# Integrated_Platform_Controller.net
KiCad netlist of a schematic drawn in Altium Designer
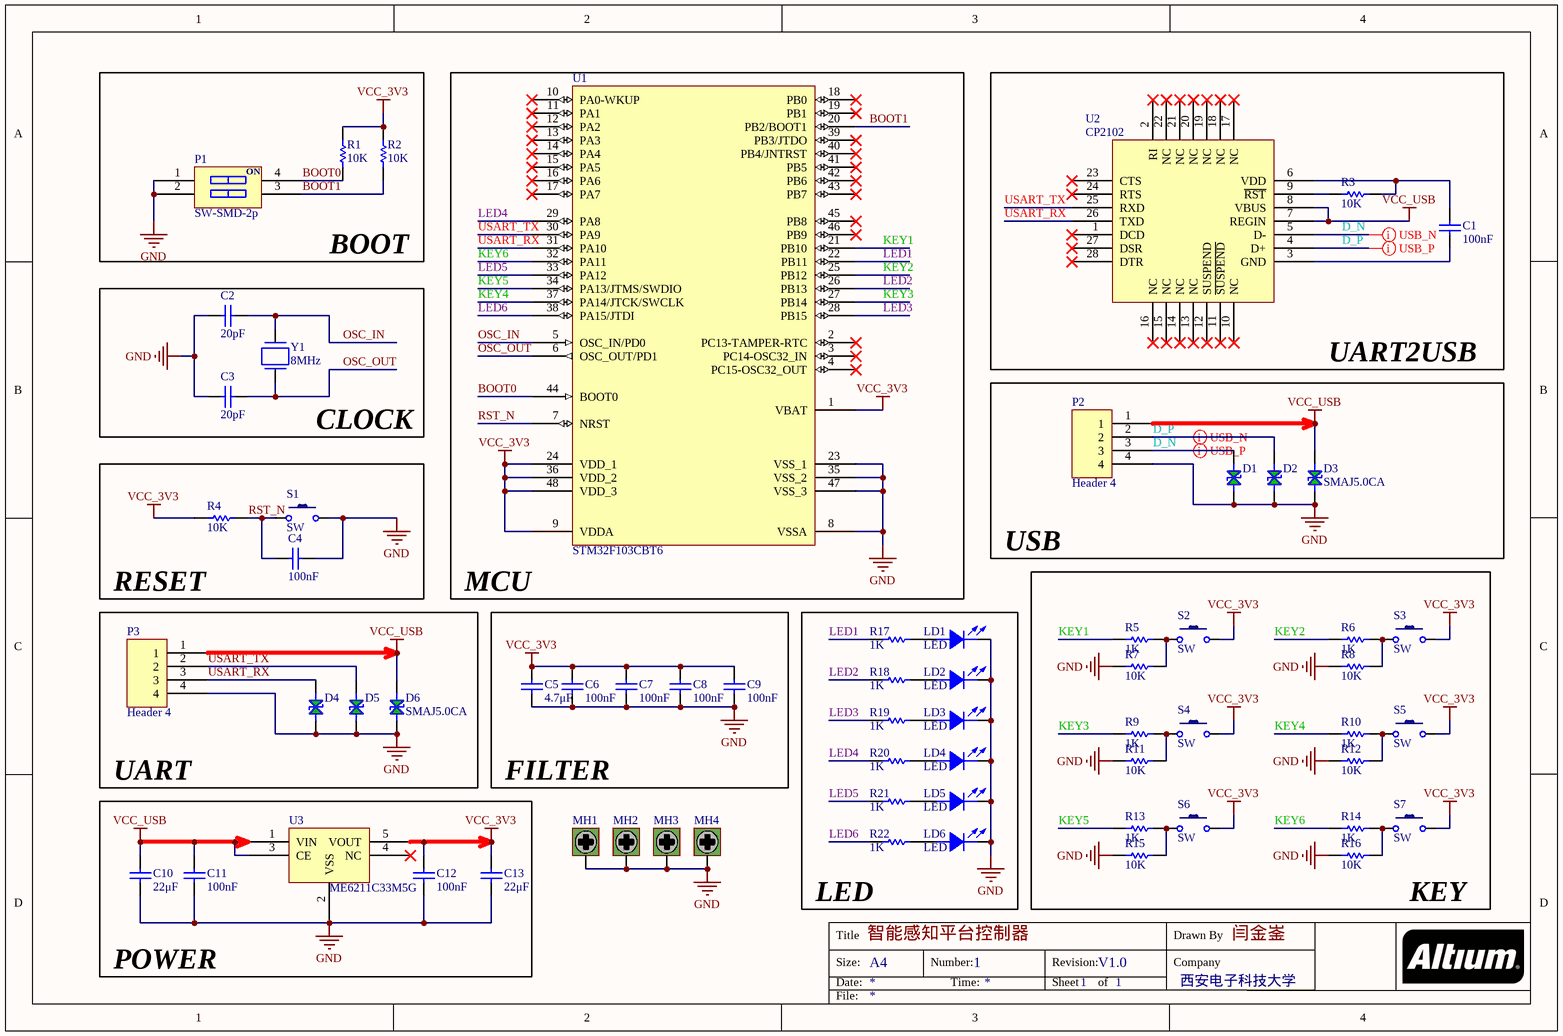
[diagram p0: Integrated_Platform_Controller.SchDoc]

(export (version "E")
  (design (tool "Eeschema 10.0.6"))
  (components
    (comp (ref "C1")
      (value "100nF")
      (footprint "C-0603")
      (description "Capacitor")
      (fields (field (name "PUBLISHER") "Altium Limited"))
      (libsource (lib "Verdvana_Library") (part "CAP"))
    )
    (comp (ref "C2")
      (value "20pF")
      (footprint "C-0603")
      (description "Capacitor")
      (fields (field (name "PUBLISHER") "Altium Limited"))
      (libsource (lib "Verdvana_Library") (part "CAP"))
    )
    (comp (ref "C3")
      (value "20pF")
      (footprint "C-0603")
      (description "Capacitor")
      (fields (field (name "PUBLISHER") "Altium Limited"))
      (libsource (lib "Verdvana_Library") (part "CAP"))
    )
    (comp (ref "C4")
      (value "100nF")
      (footprint "C-0603")
      (description "Capacitor")
      (fields (field (name "PUBLISHER") "Altium Limited"))
      (libsource (lib "Verdvana_Library") (part "CAP"))
    )
    (comp (ref "C5")
      (value "4.7μF")
      (footprint "C-0805")
      (description "Capacitor")
      (fields (field (name "PUBLISHER") "Altium Limited"))
      (libsource (lib "Verdvana_Library") (part "CAP"))
    )
    (comp (ref "C6")
      (value "100nF")
      (footprint "C-0603")
      (description "Capacitor")
      (fields (field (name "PUBLISHER") "Altium Limited"))
      (libsource (lib "Verdvana_Library") (part "CAP"))
    )
    (comp (ref "C7")
      (value "100nF")
      (footprint "C-0603")
      (description "Capacitor")
      (fields (field (name "PUBLISHER") "Altium Limited"))
      (libsource (lib "Verdvana_Library") (part "CAP"))
    )
    (comp (ref "C8")
      (value "100nF")
      (footprint "C-0603")
      (description "Capacitor")
      (fields (field (name "PUBLISHER") "Altium Limited"))
      (libsource (lib "Verdvana_Library") (part "CAP"))
    )
    (comp (ref "C9")
      (value "100nF")
      (footprint "C-0603")
      (description "Capacitor")
      (fields (field (name "PUBLISHER") "Altium Limited"))
      (libsource (lib "Verdvana_Library") (part "CAP"))
    )
    (comp (ref "C10")
      (value "22μF")
      (footprint "C-0805")
      (description "Capacitor")
      (fields (field (name "PUBLISHER") "Altium Limited"))
      (libsource (lib "Verdvana_Library") (part "CAP"))
    )
    (comp (ref "C11")
      (value "100nF")
      (footprint "C-0603")
      (description "Capacitor")
      (fields (field (name "PUBLISHER") "Altium Limited"))
      (libsource (lib "Verdvana_Library") (part "CAP"))
    )
    (comp (ref "C12")
      (value "100nF")
      (footprint "C-0603")
      (description "Capacitor")
      (fields (field (name "PUBLISHER") "Altium Limited"))
      (libsource (lib "Verdvana_Library") (part "CAP"))
    )
    (comp (ref "C13")
      (value "22μF")
      (footprint "C-0805")
      (description "Capacitor")
      (fields (field (name "PUBLISHER") "Altium Limited"))
      (libsource (lib "Verdvana_Library") (part "CAP"))
    )
    (comp (ref "D1")
      (value "SMAJ5.0CA")
      (footprint "SMA-DO-214AC")
      (description "TVS")
      (libsource (lib "Verdvana_Library") (part "TVS"))
    )
    (comp (ref "D2")
      (value "SMAJ5.0CA")
      (footprint "SMA-DO-214AC")
      (description "TVS")
      (libsource (lib "Verdvana_Library") (part "TVS"))
    )
    (comp (ref "D3")
      (value "SMAJ5.0CA")
      (footprint "SMA-DO-214AC")
      (description "TVS")
      (libsource (lib "Verdvana_Library") (part "TVS"))
    )
    (comp (ref "D4")
      (value "SMAJ5.0CA")
      (footprint "SMA-DO-214AC")
      (description "TVS")
      (libsource (lib "Verdvana_Library") (part "TVS"))
    )
    (comp (ref "D5")
      (value "SMAJ5.0CA")
      (footprint "SMA-DO-214AC")
      (description "TVS")
      (libsource (lib "Verdvana_Library") (part "TVS"))
    )
    (comp (ref "D6")
      (value "SMAJ5.0CA")
      (footprint "SMA-DO-214AC")
      (description "TVS")
      (libsource (lib "Verdvana_Library") (part "TVS"))
    )
    (comp (ref "LD1")
      (value "LED")
      (footprint "LED-RED-3MM")
      (libsource (lib "Verdvana_Library") (part "LED"))
    )
    (comp (ref "LD2")
      (value "LED")
      (footprint "LED-RED-3MM")
      (libsource (lib "Verdvana_Library") (part "LED"))
    )
    (comp (ref "LD3")
      (value "LED")
      (footprint "LED-RED-3MM")
      (libsource (lib "Verdvana_Library") (part "LED"))
    )
    (comp (ref "LD4")
      (value "LED")
      (footprint "LED-RED-3MM")
      (libsource (lib "Verdvana_Library") (part "LED"))
    )
    (comp (ref "LD5")
      (value "LED")
      (footprint "LED-RED-3MM")
      (libsource (lib "Verdvana_Library") (part "LED"))
    )
    (comp (ref "LD6")
      (value "LED")
      (footprint "LED-RED-3MM")
      (libsource (lib "Verdvana_Library") (part "LED"))
    )
    (comp (ref "MH1")
      (value "Mounting Hole 3MM")
      (footprint "MOUNT")
      (libsource (lib "Verdvana_Library") (part "Mounting Hole 3MM"))
    )
    (comp (ref "MH2")
      (value "Mounting Hole 3MM")
      (footprint "MOUNT")
      (libsource (lib "Verdvana_Library") (part "Mounting Hole 3MM"))
    )
    (comp (ref "MH3")
      (value "Mounting Hole 3MM")
      (footprint "MOUNT")
      (libsource (lib "Verdvana_Library") (part "Mounting Hole 3MM"))
    )
    (comp (ref "MH4")
      (value "Mounting Hole 3MM")
      (footprint "MOUNT")
      (libsource (lib "Verdvana_Library") (part "Mounting Hole 3MM"))
    )
    (comp (ref "P1")
      (value "SW-SMD-2p")
      (footprint "SW-2p-1.27mm")
      (description "SW-SMT-2p")
      (libsource (lib "Verdvana_Library") (part "SW-SMD-2p"))
    )
    (comp (ref "P2")
      (value "Header 4")
      (footprint "SIP4")
      (libsource (lib "Verdvana_Library") (part "Header 4"))
    )
    (comp (ref "P3")
      (value "Header 4")
      (footprint "SIP4")
      (libsource (lib "Verdvana_Library") (part "Header 4"))
    )
    (comp (ref "R1")
      (value "10K")
      (footprint "R-0603")
      (description "Potentiometer")
      (fields (field (name "PUBLISHER") "Altium Limited"))
      (libsource (lib "Verdvana_Library") (part "RES"))
    )
    (comp (ref "R2")
      (value "10K")
      (footprint "R-0603")
      (description "Potentiometer")
      (fields (field (name "PUBLISHER") "Altium Limited"))
      (libsource (lib "Verdvana_Library") (part "RES"))
    )
    (comp (ref "R3")
      (value "10K")
      (footprint "R-0603")
      (description "Potentiometer")
      (fields (field (name "PUBLISHER") "Altium Limited"))
      (libsource (lib "Verdvana_Library") (part "RES"))
    )
    (comp (ref "R4")
      (value "10K")
      (footprint "R-0603")
      (description "Potentiometer")
      (fields (field (name "PUBLISHER") "Altium Limited"))
      (libsource (lib "Verdvana_Library") (part "RES"))
    )
    (comp (ref "R5")
      (value "1K")
      (footprint "R-0603")
      (description "Potentiometer")
      (fields (field (name "PUBLISHER") "Altium Limited"))
      (libsource (lib "Verdvana_Library") (part "RES"))
    )
    (comp (ref "R6")
      (value "1K")
      (footprint "R-0603")
      (description "Potentiometer")
      (fields (field (name "PUBLISHER") "Altium Limited"))
      (libsource (lib "Verdvana_Library") (part "RES"))
    )
    (comp (ref "R7")
      (value "10K")
      (footprint "R-0603")
      (description "Potentiometer")
      (fields (field (name "PUBLISHER") "Altium Limited"))
      (libsource (lib "Verdvana_Library") (part "RES"))
    )
    (comp (ref "R8")
      (value "10K")
      (footprint "R-0603")
      (description "Potentiometer")
      (fields (field (name "PUBLISHER") "Altium Limited"))
      (libsource (lib "Verdvana_Library") (part "RES"))
    )
    (comp (ref "R9")
      (value "1K")
      (footprint "R-0603")
      (description "Potentiometer")
      (fields (field (name "PUBLISHER") "Altium Limited"))
      (libsource (lib "Verdvana_Library") (part "RES"))
    )
    (comp (ref "R10")
      (value "1K")
      (footprint "R-0603")
      (description "Potentiometer")
      (fields (field (name "PUBLISHER") "Altium Limited"))
      (libsource (lib "Verdvana_Library") (part "RES"))
    )
    (comp (ref "R11")
      (value "10K")
      (footprint "R-0603")
      (description "Potentiometer")
      (fields (field (name "PUBLISHER") "Altium Limited"))
      (libsource (lib "Verdvana_Library") (part "RES"))
    )
    (comp (ref "R12")
      (value "10K")
      (footprint "R-0603")
      (description "Potentiometer")
      (fields (field (name "PUBLISHER") "Altium Limited"))
      (libsource (lib "Verdvana_Library") (part "RES"))
    )
    (comp (ref "R13")
      (value "1K")
      (footprint "R-0603")
      (description "Potentiometer")
      (fields (field (name "PUBLISHER") "Altium Limited"))
      (libsource (lib "Verdvana_Library") (part "RES"))
    )
    (comp (ref "R14")
      (value "1K")
      (footprint "R-0603")
      (description "Potentiometer")
      (fields (field (name "PUBLISHER") "Altium Limited"))
      (libsource (lib "Verdvana_Library") (part "RES"))
    )
    (comp (ref "R15")
      (value "10K")
      (footprint "R-0603")
      (description "Potentiometer")
      (fields (field (name "PUBLISHER") "Altium Limited"))
      (libsource (lib "Verdvana_Library") (part "RES"))
    )
    (comp (ref "R16")
      (value "10K")
      (footprint "R-0603")
      (description "Potentiometer")
      (fields (field (name "PUBLISHER") "Altium Limited"))
      (libsource (lib "Verdvana_Library") (part "RES"))
    )
    (comp (ref "R17")
      (value "1K")
      (footprint "R-0603")
      (description "Potentiometer")
      (fields (field (name "PUBLISHER") "Altium Limited"))
      (libsource (lib "Verdvana_Library") (part "RES"))
    )
    (comp (ref "R18")
      (value "1K")
      (footprint "R-0603")
      (description "Potentiometer")
      (fields (field (name "PUBLISHER") "Altium Limited"))
      (libsource (lib "Verdvana_Library") (part "RES"))
    )
    (comp (ref "R19")
      (value "1K")
      (footprint "R-0603")
      (description "Potentiometer")
      (fields (field (name "PUBLISHER") "Altium Limited"))
      (libsource (lib "Verdvana_Library") (part "RES"))
    )
    (comp (ref "R20")
      (value "1K")
      (footprint "R-0603")
      (description "Potentiometer")
      (fields (field (name "PUBLISHER") "Altium Limited"))
      (libsource (lib "Verdvana_Library") (part "RES"))
    )
    (comp (ref "R21")
      (value "1K")
      (footprint "R-0603")
      (description "Potentiometer")
      (fields (field (name "PUBLISHER") "Altium Limited"))
      (libsource (lib "Verdvana_Library") (part "RES"))
    )
    (comp (ref "R22")
      (value "1K")
      (footprint "R-0603")
      (description "Potentiometer")
      (fields (field (name "PUBLISHER") "Altium Limited"))
      (libsource (lib "Verdvana_Library") (part "RES"))
    )
    (comp (ref "S1")
      (value "SW")
      (footprint "KEY-SMD_3X6")
      (description "Key")
      (libsource (lib "Verdvana_Library") (part "KEY"))
    )
    (comp (ref "S2")
      (value "SW")
      (footprint "KEY-DIP-12X12X7.3")
      (description "Key")
      (libsource (lib "Verdvana_Library") (part "KEY"))
    )
    (comp (ref "S3")
      (value "SW")
      (footprint "KEY-DIP-12X12X7.3")
      (description "Key")
      (libsource (lib "Verdvana_Library") (part "KEY"))
    )
    (comp (ref "S4")
      (value "SW")
      (footprint "KEY-DIP-12X12X7.3")
      (description "Key")
      (libsource (lib "Verdvana_Library") (part "KEY"))
    )
    (comp (ref "S5")
      (value "SW")
      (footprint "KEY-DIP-12X12X7.3")
      (description "Key")
      (libsource (lib "Verdvana_Library") (part "KEY"))
    )
    (comp (ref "S6")
      (value "SW")
      (footprint "KEY-DIP-12X12X7.3")
      (description "Key")
      (libsource (lib "Verdvana_Library") (part "KEY"))
    )
    (comp (ref "S7")
      (value "SW")
      (footprint "KEY-DIP-12X12X7.3")
      (description "Key")
      (libsource (lib "Verdvana_Library") (part "KEY"))
    )
    (comp (ref "U1")
      (value "STM32F103CBT6")
      (footprint "LQFP48")
      (description "STM32 ARM-based 32-bit MCU with 128 Kbytes Flash, 48-pin LQFP, Industrial Temperature")
      (libsource (lib "Verdvana_Library") (part "STM32F103CBT6"))
    )
    (comp (ref "U2")
      (value "CP2102")
      (footprint "QFN-28")
      (libsource (lib "Verdvana_Library") (part "CP2102"))
    )
    (comp (ref "U3")
      (value "ME6211C33M5G")
      (footprint "SOT-23-5")
      (description "ME6211H/C")
      (libsource (lib "Verdvana_Library") (part "ME6211H/C"))
    )
    (comp (ref "Y1")
      (value "8MHz")
      (footprint "XTAL-QC49/SMD")
      (description "CRYSTAL")
      (libsource (lib "Verdvana_Library") (part "XTAL"))
    )
  )
  (nets
    (net (code "1") (name "/BOOT0") (class "Default")
      (node (ref "P1") (pin "4") (pinfunction "4_4") (pintype "passive"))
      (node (ref "R1") (pin "1") (pinfunction "TOP_1") (pintype "passive"))
      (node (ref "U1") (pin "44") (pinfunction "BOOT0_44") (pintype "input"))
    )
    (net (code "2") (name "/BOOT1") (class "Default")
      (node (ref "P1") (pin "3") (pinfunction "3_3") (pintype "passive"))
      (node (ref "R2") (pin "1") (pinfunction "TOP_1") (pintype "passive"))
      (node (ref "U1") (pin "20") (pinfunction "PB2/BOOT1_20") (pintype "bidirectional"))
    )
    (net (code "3") (name "/D_N") (class "Default")
      (node (ref "D1") (pin "2") (pinfunction "K_2") (pintype "passive"))
      (node (ref "P2") (pin "3") (pinfunction "3_3") (pintype "power_in"))
      (node (ref "U2") (pin "5") (pinfunction "D-_5") (pintype "passive"))
    )
    (net (code "4") (name "/D_P") (class "Default")
      (node (ref "D2") (pin "2") (pinfunction "K_2") (pintype "passive"))
      (node (ref "P2") (pin "2") (pinfunction "2_2") (pintype "power_in"))
      (node (ref "U2") (pin "4") (pinfunction "D+_4") (pintype "passive"))
    )
    (net (code "5") (name "/KEY1") (class "Default")
      (node (ref "R5") (pin "1") (pinfunction "TOP_1") (pintype "passive"))
      (node (ref "U1") (pin "21") (pinfunction "PB10_21") (pintype "bidirectional"))
    )
    (net (code "6") (name "/KEY2") (class "Default")
      (node (ref "R6") (pin "1") (pinfunction "TOP_1") (pintype "passive"))
      (node (ref "U1") (pin "25") (pinfunction "PB12_25") (pintype "bidirectional"))
    )
    (net (code "7") (name "/KEY3") (class "Default")
      (node (ref "R9") (pin "1") (pinfunction "TOP_1") (pintype "passive"))
      (node (ref "U1") (pin "27") (pinfunction "PB14_27") (pintype "bidirectional"))
    )
    (net (code "8") (name "/KEY4") (class "Default")
      (node (ref "R10") (pin "1") (pinfunction "TOP_1") (pintype "passive"))
      (node (ref "U1") (pin "37") (pinfunction "PA14/JTCK/SWCLK_37") (pintype "bidirectional"))
    )
    (net (code "9") (name "/KEY5") (class "Default")
      (node (ref "R13") (pin "1") (pinfunction "TOP_1") (pintype "passive"))
      (node (ref "U1") (pin "34") (pinfunction "PA13/JTMS/SWDIO_34") (pintype "bidirectional"))
    )
    (net (code "10") (name "/KEY6") (class "Default")
      (node (ref "R14") (pin "1") (pinfunction "TOP_1") (pintype "passive"))
      (node (ref "U1") (pin "32") (pinfunction "PA11_32") (pintype "bidirectional"))
    )
    (net (code "11") (name "/LED1") (class "Default")
      (node (ref "R17") (pin "1") (pinfunction "TOP_1") (pintype "passive"))
      (node (ref "U1") (pin "22") (pinfunction "PB11_22") (pintype "bidirectional"))
    )
    (net (code "12") (name "/LED2") (class "Default")
      (node (ref "R18") (pin "1") (pinfunction "TOP_1") (pintype "passive"))
      (node (ref "U1") (pin "26") (pinfunction "PB13_26") (pintype "bidirectional"))
    )
    (net (code "13") (name "/LED3") (class "Default")
      (node (ref "R19") (pin "1") (pinfunction "TOP_1") (pintype "passive"))
      (node (ref "U1") (pin "28") (pinfunction "PB15_28") (pintype "bidirectional"))
    )
    (net (code "14") (name "/LED4") (class "Default")
      (node (ref "R20") (pin "1") (pinfunction "TOP_1") (pintype "passive"))
      (node (ref "U1") (pin "29") (pinfunction "PA8_29") (pintype "bidirectional"))
    )
    (net (code "15") (name "/LED5") (class "Default")
      (node (ref "R21") (pin "1") (pinfunction "TOP_1") (pintype "passive"))
      (node (ref "U1") (pin "33") (pinfunction "PA12_33") (pintype "bidirectional"))
    )
    (net (code "16") (name "/LED6") (class "Default")
      (node (ref "R22") (pin "1") (pinfunction "TOP_1") (pintype "passive"))
      (node (ref "U1") (pin "38") (pinfunction "PA15/JTDI_38") (pintype "bidirectional"))
    )
    (net (code "17") (name "/OSC_IN") (class "Default")
      (node (ref "C2") (pin "2") (pinfunction "2_2") (pintype "passive"))
      (node (ref "U1") (pin "5") (pinfunction "OSC_IN/PD0_5") (pintype "input"))
      (node (ref "Y1") (pin "2") (pinfunction "2_2") (pintype "passive"))
    )
    (net (code "18") (name "/OSC_OUT") (class "Default")
      (node (ref "C3") (pin "2") (pinfunction "2_2") (pintype "passive"))
      (node (ref "U1") (pin "6") (pinfunction "OSC_OUT/PD1_6") (pintype "output"))
      (node (ref "Y1") (pin "1") (pinfunction "1_1") (pintype "passive"))
    )
    (net (code "19") (name "/RST_N") (class "Default")
      (node (ref "C4") (pin "1") (pinfunction "1_1") (pintype "passive"))
      (node (ref "R4") (pin "2") (pinfunction "BOT_2") (pintype "passive"))
      (node (ref "S1") (pin "1") (pinfunction "1_1") (pintype "passive"))
      (node (ref "U1") (pin "7") (pinfunction "NRST_7") (pintype "bidirectional"))
    )
    (net (code "20") (name "/USART_RX") (class "Default")
      (node (ref "D4") (pin "2") (pinfunction "K_2") (pintype "passive"))
      (node (ref "P3") (pin "3") (pinfunction "3_3") (pintype "power_in"))
      (node (ref "U1") (pin "31") (pinfunction "PA10_31") (pintype "bidirectional"))
      (node (ref "U2") (pin "26") (pinfunction "TXD_26") (pintype "passive"))
    )
    (net (code "21") (name "/USART_TX") (class "Default")
      (node (ref "D5") (pin "2") (pinfunction "K_2") (pintype "passive"))
      (node (ref "P3") (pin "2") (pinfunction "2_2") (pintype "power_in"))
      (node (ref "U1") (pin "30") (pinfunction "PA9_30") (pintype "bidirectional"))
      (node (ref "U2") (pin "25") (pinfunction "RXD_25") (pintype "passive"))
    )
    (net (code "22") (name "GND") (class "Default")
      (node (ref "C10") (pin "1") (pinfunction "1_1") (pintype "passive"))
      (node (ref "C11") (pin "1") (pinfunction "1_1") (pintype "passive"))
      (node (ref "C12") (pin "1") (pinfunction "1_1") (pintype "passive"))
      (node (ref "C13") (pin "1") (pinfunction "1_1") (pintype "passive"))
      (node (ref "C2") (pin "1") (pinfunction "1_1") (pintype "passive"))
      (node (ref "C3") (pin "1") (pinfunction "1_1") (pintype "passive"))
      (node (ref "C4") (pin "2") (pinfunction "2_2") (pintype "passive"))
      (node (ref "C5") (pin "1") (pinfunction "1_1") (pintype "passive"))
      (node (ref "C6") (pin "1") (pinfunction "1_1") (pintype "passive"))
      (node (ref "C7") (pin "1") (pinfunction "1_1") (pintype "passive"))
      (node (ref "C8") (pin "1") (pinfunction "1_1") (pintype "passive"))
      (node (ref "C9") (pin "1") (pinfunction "1_1") (pintype "passive"))
      (node (ref "D1") (pin "1") (pinfunction "A_1") (pintype "passive"))
      (node (ref "D2") (pin "1") (pinfunction "A_1") (pintype "passive"))
      (node (ref "D3") (pin "1") (pinfunction "A_1") (pintype "passive"))
      (node (ref "D4") (pin "1") (pinfunction "A_1") (pintype "passive"))
      (node (ref "D5") (pin "1") (pinfunction "A_1") (pintype "passive"))
      (node (ref "D6") (pin "1") (pinfunction "A_1") (pintype "passive"))
      (node (ref "LD1") (pin "2") (pinfunction "CATHODE_2") (pintype "passive"))
      (node (ref "LD2") (pin "2") (pinfunction "CATHODE_2") (pintype "passive"))
      (node (ref "LD3") (pin "2") (pinfunction "CATHODE_2") (pintype "passive"))
      (node (ref "LD4") (pin "2") (pinfunction "CATHODE_2") (pintype "passive"))
      (node (ref "LD5") (pin "2") (pinfunction "CATHODE_2") (pintype "passive"))
      (node (ref "LD6") (pin "2") (pinfunction "CATHODE_2") (pintype "passive"))
      (node (ref "MH1") (pin "1") (pinfunction "1_1") (pintype "passive"))
      (node (ref "MH2") (pin "1") (pinfunction "1_1") (pintype "passive"))
      (node (ref "MH3") (pin "1") (pinfunction "1_1") (pintype "passive"))
      (node (ref "MH4") (pin "1") (pinfunction "1_1") (pintype "passive"))
      (node (ref "P1") (pin "1") (pinfunction "1_1") (pintype "passive"))
      (node (ref "P1") (pin "2") (pinfunction "2_2") (pintype "passive"))
      (node (ref "P2") (pin "4") (pinfunction "4_4") (pintype "power_in"))
      (node (ref "P3") (pin "4") (pinfunction "4_4") (pintype "power_in"))
      (node (ref "R11") (pin "1") (pinfunction "TOP_1") (pintype "passive"))
      (node (ref "R12") (pin "1") (pinfunction "TOP_1") (pintype "passive"))
      (node (ref "R15") (pin "1") (pinfunction "TOP_1") (pintype "passive"))
      (node (ref "R16") (pin "1") (pinfunction "TOP_1") (pintype "passive"))
      (node (ref "R7") (pin "1") (pinfunction "TOP_1") (pintype "passive"))
      (node (ref "R8") (pin "1") (pinfunction "TOP_1") (pintype "passive"))
      (node (ref "S1") (pin "2") (pinfunction "2_2") (pintype "passive"))
      (node (ref "U1") (pin "23") (pinfunction "VSS_1_23") (pintype "power_in"))
      (node (ref "U1") (pin "35") (pinfunction "VSS_2_35") (pintype "power_in"))
      (node (ref "U1") (pin "47") (pinfunction "VSS_3_47") (pintype "power_in"))
      (node (ref "U1") (pin "8") (pinfunction "VSSA_8") (pintype "power_in"))
      (node (ref "U3") (pin "2") (pinfunction "VSS_2") (pintype "passive"))
    )
    (net (code "23") (name "Net-(LD1-ANODE)") (class "Default")
      (node (ref "LD1") (pin "1") (pinfunction "ANODE_1") (pintype "passive"))
      (node (ref "R17") (pin "2") (pinfunction "BOT_2") (pintype "passive"))
    )
    (net (code "24") (name "Net-(LD2-ANODE)") (class "Default")
      (node (ref "LD2") (pin "1") (pinfunction "ANODE_1") (pintype "passive"))
      (node (ref "R18") (pin "2") (pinfunction "BOT_2") (pintype "passive"))
    )
    (net (code "25") (name "Net-(LD3-ANODE)") (class "Default")
      (node (ref "LD3") (pin "1") (pinfunction "ANODE_1") (pintype "passive"))
      (node (ref "R19") (pin "2") (pinfunction "BOT_2") (pintype "passive"))
    )
    (net (code "26") (name "Net-(LD4-ANODE)") (class "Default")
      (node (ref "LD4") (pin "1") (pinfunction "ANODE_1") (pintype "passive"))
      (node (ref "R20") (pin "2") (pinfunction "BOT_2") (pintype "passive"))
    )
    (net (code "27") (name "Net-(LD5-ANODE)") (class "Default")
      (node (ref "LD5") (pin "1") (pinfunction "ANODE_1") (pintype "passive"))
      (node (ref "R21") (pin "2") (pinfunction "BOT_2") (pintype "passive"))
    )
    (net (code "28") (name "Net-(LD6-ANODE)") (class "Default")
      (node (ref "LD6") (pin "1") (pinfunction "ANODE_1") (pintype "passive"))
      (node (ref "R22") (pin "2") (pinfunction "BOT_2") (pintype "passive"))
    )
    (net (code "29") (name "Net-(R3-BOT)") (class "Default")
      (node (ref "C1") (pin "2") (pinfunction "2_2") (pintype "passive"))
      (node (ref "R3") (pin "2") (pinfunction "BOT_2") (pintype "passive"))
      (node (ref "U2") (pin "6") (pinfunction "VDD_6") (pintype "passive"))
    )
    (net (code "30") (name "Net-(R3-TOP)") (class "Default")
      (node (ref "R3") (pin "1") (pinfunction "TOP_1") (pintype "passive"))
      (node (ref "U2") (pin "9") (pinfunction "~{RST}_9") (pintype "passive"))
    )
    (net (code "31") (name "Net-(R5-BOT)") (class "Default")
      (node (ref "R5") (pin "2") (pinfunction "BOT_2") (pintype "passive"))
      (node (ref "R7") (pin "2") (pinfunction "BOT_2") (pintype "passive"))
      (node (ref "S2") (pin "1") (pinfunction "1_1") (pintype "passive"))
    )
    (net (code "32") (name "Net-(R6-BOT)") (class "Default")
      (node (ref "R6") (pin "2") (pinfunction "BOT_2") (pintype "passive"))
      (node (ref "R8") (pin "2") (pinfunction "BOT_2") (pintype "passive"))
      (node (ref "S3") (pin "1") (pinfunction "1_1") (pintype "passive"))
    )
    (net (code "33") (name "Net-(R10-BOT)") (class "Default")
      (node (ref "R10") (pin "2") (pinfunction "BOT_2") (pintype "passive"))
      (node (ref "R12") (pin "2") (pinfunction "BOT_2") (pintype "passive"))
      (node (ref "S5") (pin "1") (pinfunction "1_1") (pintype "passive"))
    )
    (net (code "34") (name "Net-(R11-BOT)") (class "Default")
      (node (ref "R11") (pin "2") (pinfunction "BOT_2") (pintype "passive"))
      (node (ref "R9") (pin "2") (pinfunction "BOT_2") (pintype "passive"))
      (node (ref "S4") (pin "1") (pinfunction "1_1") (pintype "passive"))
    )
    (net (code "35") (name "Net-(R13-BOT)") (class "Default")
      (node (ref "R13") (pin "2") (pinfunction "BOT_2") (pintype "passive"))
      (node (ref "R15") (pin "2") (pinfunction "BOT_2") (pintype "passive"))
      (node (ref "S6") (pin "1") (pinfunction "1_1") (pintype "passive"))
    )
    (net (code "36") (name "Net-(R14-BOT)") (class "Default")
      (node (ref "R14") (pin "2") (pinfunction "BOT_2") (pintype "passive"))
      (node (ref "R16") (pin "2") (pinfunction "BOT_2") (pintype "passive"))
      (node (ref "S7") (pin "1") (pinfunction "1_1") (pintype "passive"))
    )
    (net (code "37") (name "Net-(U2-GND)") (class "Default")
      (node (ref "C1") (pin "1") (pinfunction "1_1") (pintype "passive"))
      (node (ref "U2") (pin "3") (pinfunction "GND_3") (pintype "passive"))
    )
    (net (code "38") (name "VCC_3V3") (class "Default")
      (node (ref "C12") (pin "2") (pinfunction "2_2") (pintype "passive"))
      (node (ref "C13") (pin "2") (pinfunction "2_2") (pintype "passive"))
      (node (ref "C5") (pin "2") (pinfunction "2_2") (pintype "passive"))
      (node (ref "C6") (pin "2") (pinfunction "2_2") (pintype "passive"))
      (node (ref "C7") (pin "2") (pinfunction "2_2") (pintype "passive"))
      (node (ref "C8") (pin "2") (pinfunction "2_2") (pintype "passive"))
      (node (ref "C9") (pin "2") (pinfunction "2_2") (pintype "passive"))
      (node (ref "R1") (pin "2") (pinfunction "BOT_2") (pintype "passive"))
      (node (ref "R2") (pin "2") (pinfunction "BOT_2") (pintype "passive"))
      (node (ref "R4") (pin "1") (pinfunction "TOP_1") (pintype "passive"))
      (node (ref "S2") (pin "2") (pinfunction "2_2") (pintype "passive"))
      (node (ref "S3") (pin "2") (pinfunction "2_2") (pintype "passive"))
      (node (ref "S4") (pin "2") (pinfunction "2_2") (pintype "passive"))
      (node (ref "S5") (pin "2") (pinfunction "2_2") (pintype "passive"))
      (node (ref "S6") (pin "2") (pinfunction "2_2") (pintype "passive"))
      (node (ref "S7") (pin "2") (pinfunction "2_2") (pintype "passive"))
      (node (ref "U1") (pin "1") (pinfunction "VBAT_1") (pintype "power_in"))
      (node (ref "U1") (pin "24") (pinfunction "VDD_1_24") (pintype "power_in"))
      (node (ref "U1") (pin "36") (pinfunction "VDD_2_36") (pintype "power_in"))
      (node (ref "U1") (pin "48") (pinfunction "VDD_3_48") (pintype "power_in"))
      (node (ref "U1") (pin "9") (pinfunction "VDDA_9") (pintype "power_in"))
      (node (ref "U3") (pin "5") (pinfunction "VOUT_5") (pintype "passive"))
    )
    (net (code "39") (name "VCC_USB") (class "Default")
      (node (ref "C10") (pin "2") (pinfunction "2_2") (pintype "passive"))
      (node (ref "C11") (pin "2") (pinfunction "2_2") (pintype "passive"))
      (node (ref "D3") (pin "2") (pinfunction "K_2") (pintype "passive"))
      (node (ref "D6") (pin "2") (pinfunction "K_2") (pintype "passive"))
      (node (ref "P2") (pin "1") (pinfunction "1_1") (pintype "power_in"))
      (node (ref "P3") (pin "1") (pinfunction "1_1") (pintype "power_in"))
      (node (ref "U2") (pin "7") (pinfunction "REGIN_7") (pintype "passive"))
      (node (ref "U2") (pin "8") (pinfunction "VBUS_8") (pintype "passive"))
      (node (ref "U3") (pin "1") (pinfunction "VIN_1") (pintype "passive"))
      (node (ref "U3") (pin "3") (pinfunction "CE_3") (pintype "passive"))
    )
    (net (code "40") (name "unconnected-(U1-PA0-WKUP-Pad10)") (class "Default")
      (node (ref "U1") (pin "10") (pinfunction "PA0-WKUP_10") (pintype "bidirectional+no_connect"))
    )
    (net (code "41") (name "unconnected-(U1-PA1-Pad11)") (class "Default")
      (node (ref "U1") (pin "11") (pinfunction "PA1_11") (pintype "bidirectional+no_connect"))
    )
    (net (code "42") (name "unconnected-(U1-PA2-Pad12)") (class "Default")
      (node (ref "U1") (pin "12") (pinfunction "PA2_12") (pintype "bidirectional+no_connect"))
    )
    (net (code "43") (name "unconnected-(U1-PA3-Pad13)") (class "Default")
      (node (ref "U1") (pin "13") (pinfunction "PA3_13") (pintype "bidirectional+no_connect"))
    )
    (net (code "44") (name "unconnected-(U1-PA4-Pad14)") (class "Default")
      (node (ref "U1") (pin "14") (pinfunction "PA4_14") (pintype "bidirectional+no_connect"))
    )
    (net (code "45") (name "unconnected-(U1-PA5-Pad15)") (class "Default")
      (node (ref "U1") (pin "15") (pinfunction "PA5_15") (pintype "bidirectional+no_connect"))
    )
    (net (code "46") (name "unconnected-(U1-PA6-Pad16)") (class "Default")
      (node (ref "U1") (pin "16") (pinfunction "PA6_16") (pintype "bidirectional+no_connect"))
    )
    (net (code "47") (name "unconnected-(U1-PA7-Pad17)") (class "Default")
      (node (ref "U1") (pin "17") (pinfunction "PA7_17") (pintype "bidirectional+no_connect"))
    )
    (net (code "48") (name "unconnected-(U1-PB0-Pad18)") (class "Default")
      (node (ref "U1") (pin "18") (pinfunction "PB0_18") (pintype "bidirectional+no_connect"))
    )
    (net (code "49") (name "unconnected-(U1-PB1-Pad19)") (class "Default")
      (node (ref "U1") (pin "19") (pinfunction "PB1_19") (pintype "bidirectional+no_connect"))
    )
    (net (code "50") (name "unconnected-(U1-PB3{slash}JTDO-Pad39)") (class "Default")
      (node (ref "U1") (pin "39") (pinfunction "PB3/JTDO_39") (pintype "bidirectional+no_connect"))
    )
    (net (code "51") (name "unconnected-(U1-PB4{slash}JNTRST-Pad40)") (class "Default")
      (node (ref "U1") (pin "40") (pinfunction "PB4/JNTRST_40") (pintype "bidirectional+no_connect"))
    )
    (net (code "52") (name "unconnected-(U1-PB5-Pad41)") (class "Default")
      (node (ref "U1") (pin "41") (pinfunction "PB5_41") (pintype "bidirectional+no_connect"))
    )
    (net (code "53") (name "unconnected-(U1-PB6-Pad42)") (class "Default")
      (node (ref "U1") (pin "42") (pinfunction "PB6_42") (pintype "bidirectional+no_connect"))
    )
    (net (code "54") (name "unconnected-(U1-PB7-Pad43)") (class "Default")
      (node (ref "U1") (pin "43") (pinfunction "PB7_43") (pintype "bidirectional+no_connect"))
    )
    (net (code "55") (name "unconnected-(U1-PB8-Pad45)") (class "Default")
      (node (ref "U1") (pin "45") (pinfunction "PB8_45") (pintype "bidirectional+no_connect"))
    )
    (net (code "56") (name "unconnected-(U1-PB9-Pad46)") (class "Default")
      (node (ref "U1") (pin "46") (pinfunction "PB9_46") (pintype "bidirectional+no_connect"))
    )
    (net (code "57") (name "unconnected-(U1-PC13-TAMPER-RTC-Pad2)") (class "Default")
      (node (ref "U1") (pin "2") (pinfunction "PC13-TAMPER-RTC_2") (pintype "bidirectional+no_connect"))
    )
    (net (code "58") (name "unconnected-(U1-PC14-OSC32_IN-Pad3)") (class "Default")
      (node (ref "U1") (pin "3") (pinfunction "PC14-OSC32_IN_3") (pintype "bidirectional+no_connect"))
    )
    (net (code "59") (name "unconnected-(U1-PC15-OSC32_OUT-Pad4)") (class "Default")
      (node (ref "U1") (pin "4") (pinfunction "PC15-OSC32_OUT_4") (pintype "bidirectional+no_connect"))
    )
    (net (code "60") (name "unconnected-(U2-CTS-Pad23)") (class "Default")
      (node (ref "U2") (pin "23") (pinfunction "CTS_23") (pintype "passive+no_connect"))
    )
    (net (code "61") (name "unconnected-(U2-DCD-Pad1)") (class "Default")
      (node (ref "U2") (pin "1") (pinfunction "DCD_1") (pintype "passive+no_connect"))
    )
    (net (code "62") (name "unconnected-(U2-DSR-Pad27)") (class "Default")
      (node (ref "U2") (pin "27") (pinfunction "DSR_27") (pintype "passive+no_connect"))
    )
    (net (code "63") (name "unconnected-(U2-DTR-Pad28)") (class "Default")
      (node (ref "U2") (pin "28") (pinfunction "DTR_28") (pintype "passive+no_connect"))
    )
    (net (code "64") (name "unconnected-(U2-NC-Pad10)") (class "Default")
      (node (ref "U2") (pin "10") (pinfunction "NC_10") (pintype "passive+no_connect"))
    )
    (net (code "65") (name "unconnected-(U2-NC-Pad13)") (class "Default")
      (node (ref "U2") (pin "13") (pinfunction "NC_13") (pintype "passive+no_connect"))
    )
    (net (code "66") (name "unconnected-(U2-NC-Pad14)") (class "Default")
      (node (ref "U2") (pin "14") (pinfunction "NC_14") (pintype "passive+no_connect"))
    )
    (net (code "67") (name "unconnected-(U2-NC-Pad15)") (class "Default")
      (node (ref "U2") (pin "15") (pinfunction "NC_15") (pintype "passive+no_connect"))
    )
    (net (code "68") (name "unconnected-(U2-NC-Pad16)") (class "Default")
      (node (ref "U2") (pin "16") (pinfunction "NC_16") (pintype "passive+no_connect"))
    )
    (net (code "69") (name "unconnected-(U2-NC-Pad17)") (class "Default")
      (node (ref "U2") (pin "17") (pinfunction "NC_17") (pintype "passive+no_connect"))
    )
    (net (code "70") (name "unconnected-(U2-NC-Pad18)") (class "Default")
      (node (ref "U2") (pin "18") (pinfunction "NC_18") (pintype "passive+no_connect"))
    )
    (net (code "71") (name "unconnected-(U2-NC-Pad19)") (class "Default")
      (node (ref "U2") (pin "19") (pinfunction "NC_19") (pintype "passive+no_connect"))
    )
    (net (code "72") (name "unconnected-(U2-NC-Pad20)") (class "Default")
      (node (ref "U2") (pin "20") (pinfunction "NC_20") (pintype "passive+no_connect"))
    )
    (net (code "73") (name "unconnected-(U2-NC-Pad21)") (class "Default")
      (node (ref "U2") (pin "21") (pinfunction "NC_21") (pintype "passive+no_connect"))
    )
    (net (code "74") (name "unconnected-(U2-NC-Pad22)") (class "Default")
      (node (ref "U2") (pin "22") (pinfunction "NC_22") (pintype "passive+no_connect"))
    )
    (net (code "75") (name "unconnected-(U2-RI-Pad2)") (class "Default")
      (node (ref "U2") (pin "2") (pinfunction "RI_2") (pintype "passive+no_connect"))
    )
    (net (code "76") (name "unconnected-(U2-RTS-Pad24)") (class "Default")
      (node (ref "U2") (pin "24") (pinfunction "RTS_24") (pintype "passive+no_connect"))
    )
    (net (code "77") (name "unconnected-(U2-SUSPEND-Pad12)") (class "Default")
      (node (ref "U2") (pin "12") (pinfunction "SUSPEND_12") (pintype "passive+no_connect"))
    )
    (net (code "78") (name "unconnected-(U2-~{SUSPEND}-Pad11)") (class "Default")
      (node (ref "U2") (pin "11") (pinfunction "~{SUSPEND}_11") (pintype "passive+no_connect"))
    )
    (net (code "79") (name "unconnected-(U3-NC-Pad4)") (class "Default")
      (node (ref "U3") (pin "4") (pinfunction "NC_4") (pintype "passive+no_connect"))
    )
  )
)
